# Electro.net
KiCad netlist of a schematic drawn in Altium Designer
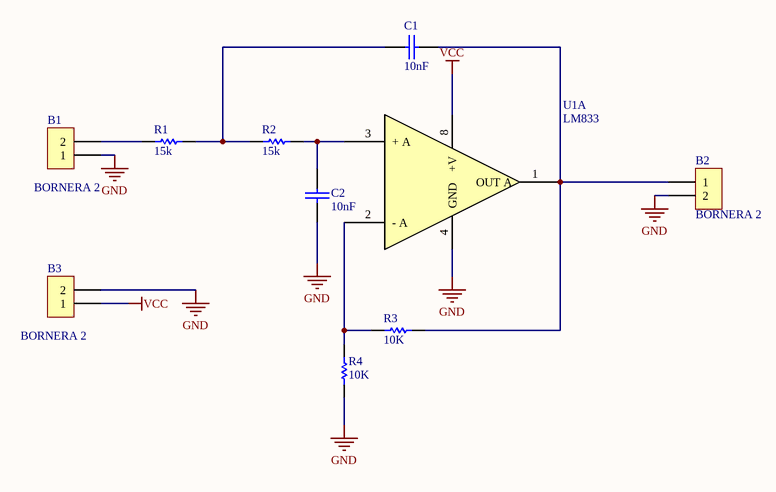
[diagram p0: Electro.SchDoc]

(export (version "E")
  (design (tool "Eeschema 10.0.6"))
  (components
    (comp (ref "B1")
      (value "BORNERA 2")
      (footprint "BORNERA2")
      (libsource (lib "LIBEBAL") (part "BORNERA 2"))
    )
    (comp (ref "B2") (value "BORNERA 2") (footprint "BORNERA2") (libsource (lib "") (part "BORNERA 2_1")))
    (comp (ref "B3")
      (value "BORNERA 2")
      (footprint "BORNERA2")
      (libsource (lib "LIBEBAL") (part "BORNERA 2"))
    )
    (comp (ref "C1") (value "10nF") (footprint "CAP200") (libsource (lib "LIBEBAL") (part "CAP")))
    (comp (ref "C2") (value "10nF") (footprint "CAP200") (libsource (lib "LIBEBAL") (part "CAP")))
    (comp (ref "R1") (value "15k") (footprint "RES400") (libsource (lib "LIBEBAL") (part "RES")))
    (comp (ref "R2") (value "15k") (footprint "RES400") (libsource (lib "LIBEBAL") (part "RES")))
    (comp (ref "R3") (value "10K") (footprint "RES400") (libsource (lib "LIBEBAL") (part "RES")))
    (comp (ref "R4") (value "10K") (footprint "RES400") (libsource (lib "LIBEBAL") (part "RES")))
    (comp (ref "U1")
      (value "LM833")
      (footprint "DIP8")
      (description "Dual Audio Operational Amplifier")
      (libsource (lib "LIBEBAL") (part "LM833"))
    )
  )
  (nets
    (net (code "1") (name "GND") (class "Default")
      (node (ref "B1") (pin "1") (pinfunction "1_1") (pintype "passive"))
      (node (ref "B2") (pin "2") (pinfunction "2_2") (pintype "passive"))
      (node (ref "B3") (pin "2") (pinfunction "2_2") (pintype "passive"))
      (node (ref "C2") (pin "1") (pinfunction "1_1") (pintype "passive"))
      (node (ref "R4") (pin "1") (pinfunction "1_1") (pintype "passive"))
      (node (ref "U1") (pin "4") (pinfunction "GND_4") (pintype "passive"))
    )
    (net (code "2") (name "Net-(B1-Pad2)") (class "Default")
      (node (ref "B1") (pin "2") (pinfunction "2_2") (pintype "passive"))
      (node (ref "R1") (pin "1") (pinfunction "1_1") (pintype "passive"))
    )
    (net (code "3") (name "Net-(C1-Pad1)") (class "Default")
      (node (ref "C1") (pin "1") (pinfunction "1_1") (pintype "passive"))
      (node (ref "R1") (pin "2") (pinfunction "2_2") (pintype "passive"))
      (node (ref "R2") (pin "1") (pinfunction "1_1") (pintype "passive"))
    )
    (net (code "4") (name "Net-(U1A-+_A)") (class "Default")
      (node (ref "C2") (pin "2") (pinfunction "2_2") (pintype "passive"))
      (node (ref "R2") (pin "2") (pinfunction "2_2") (pintype "passive"))
      (node (ref "U1") (pin "3") (pinfunction "+_A_3") (pintype "passive"))
    )
    (net (code "5") (name "Net-(U1A--_A)") (class "Default")
      (node (ref "R3") (pin "1") (pinfunction "1_1") (pintype "passive"))
      (node (ref "R4") (pin "2") (pinfunction "2_2") (pintype "passive"))
      (node (ref "U1") (pin "2") (pinfunction "-_A_2") (pintype "passive"))
    )
    (net (code "6") (name "Net-(U1A-OUT_A)") (class "Default")
      (node (ref "B2") (pin "1") (pinfunction "1_1") (pintype "passive"))
      (node (ref "C1") (pin "2") (pinfunction "2_2") (pintype "passive"))
      (node (ref "R3") (pin "2") (pinfunction "2_2") (pintype "passive"))
      (node (ref "U1") (pin "1") (pinfunction "OUT_A_1") (pintype "passive"))
    )
    (net (code "7") (name "VCC") (class "Default")
      (node (ref "B3") (pin "1") (pinfunction "1_1") (pintype "passive"))
      (node (ref "U1") (pin "8") (pinfunction "+V_8") (pintype "passive"))
    )
  )
)
